# MCU.net
KiCad netlist of a schematic drawn in Altium Designer
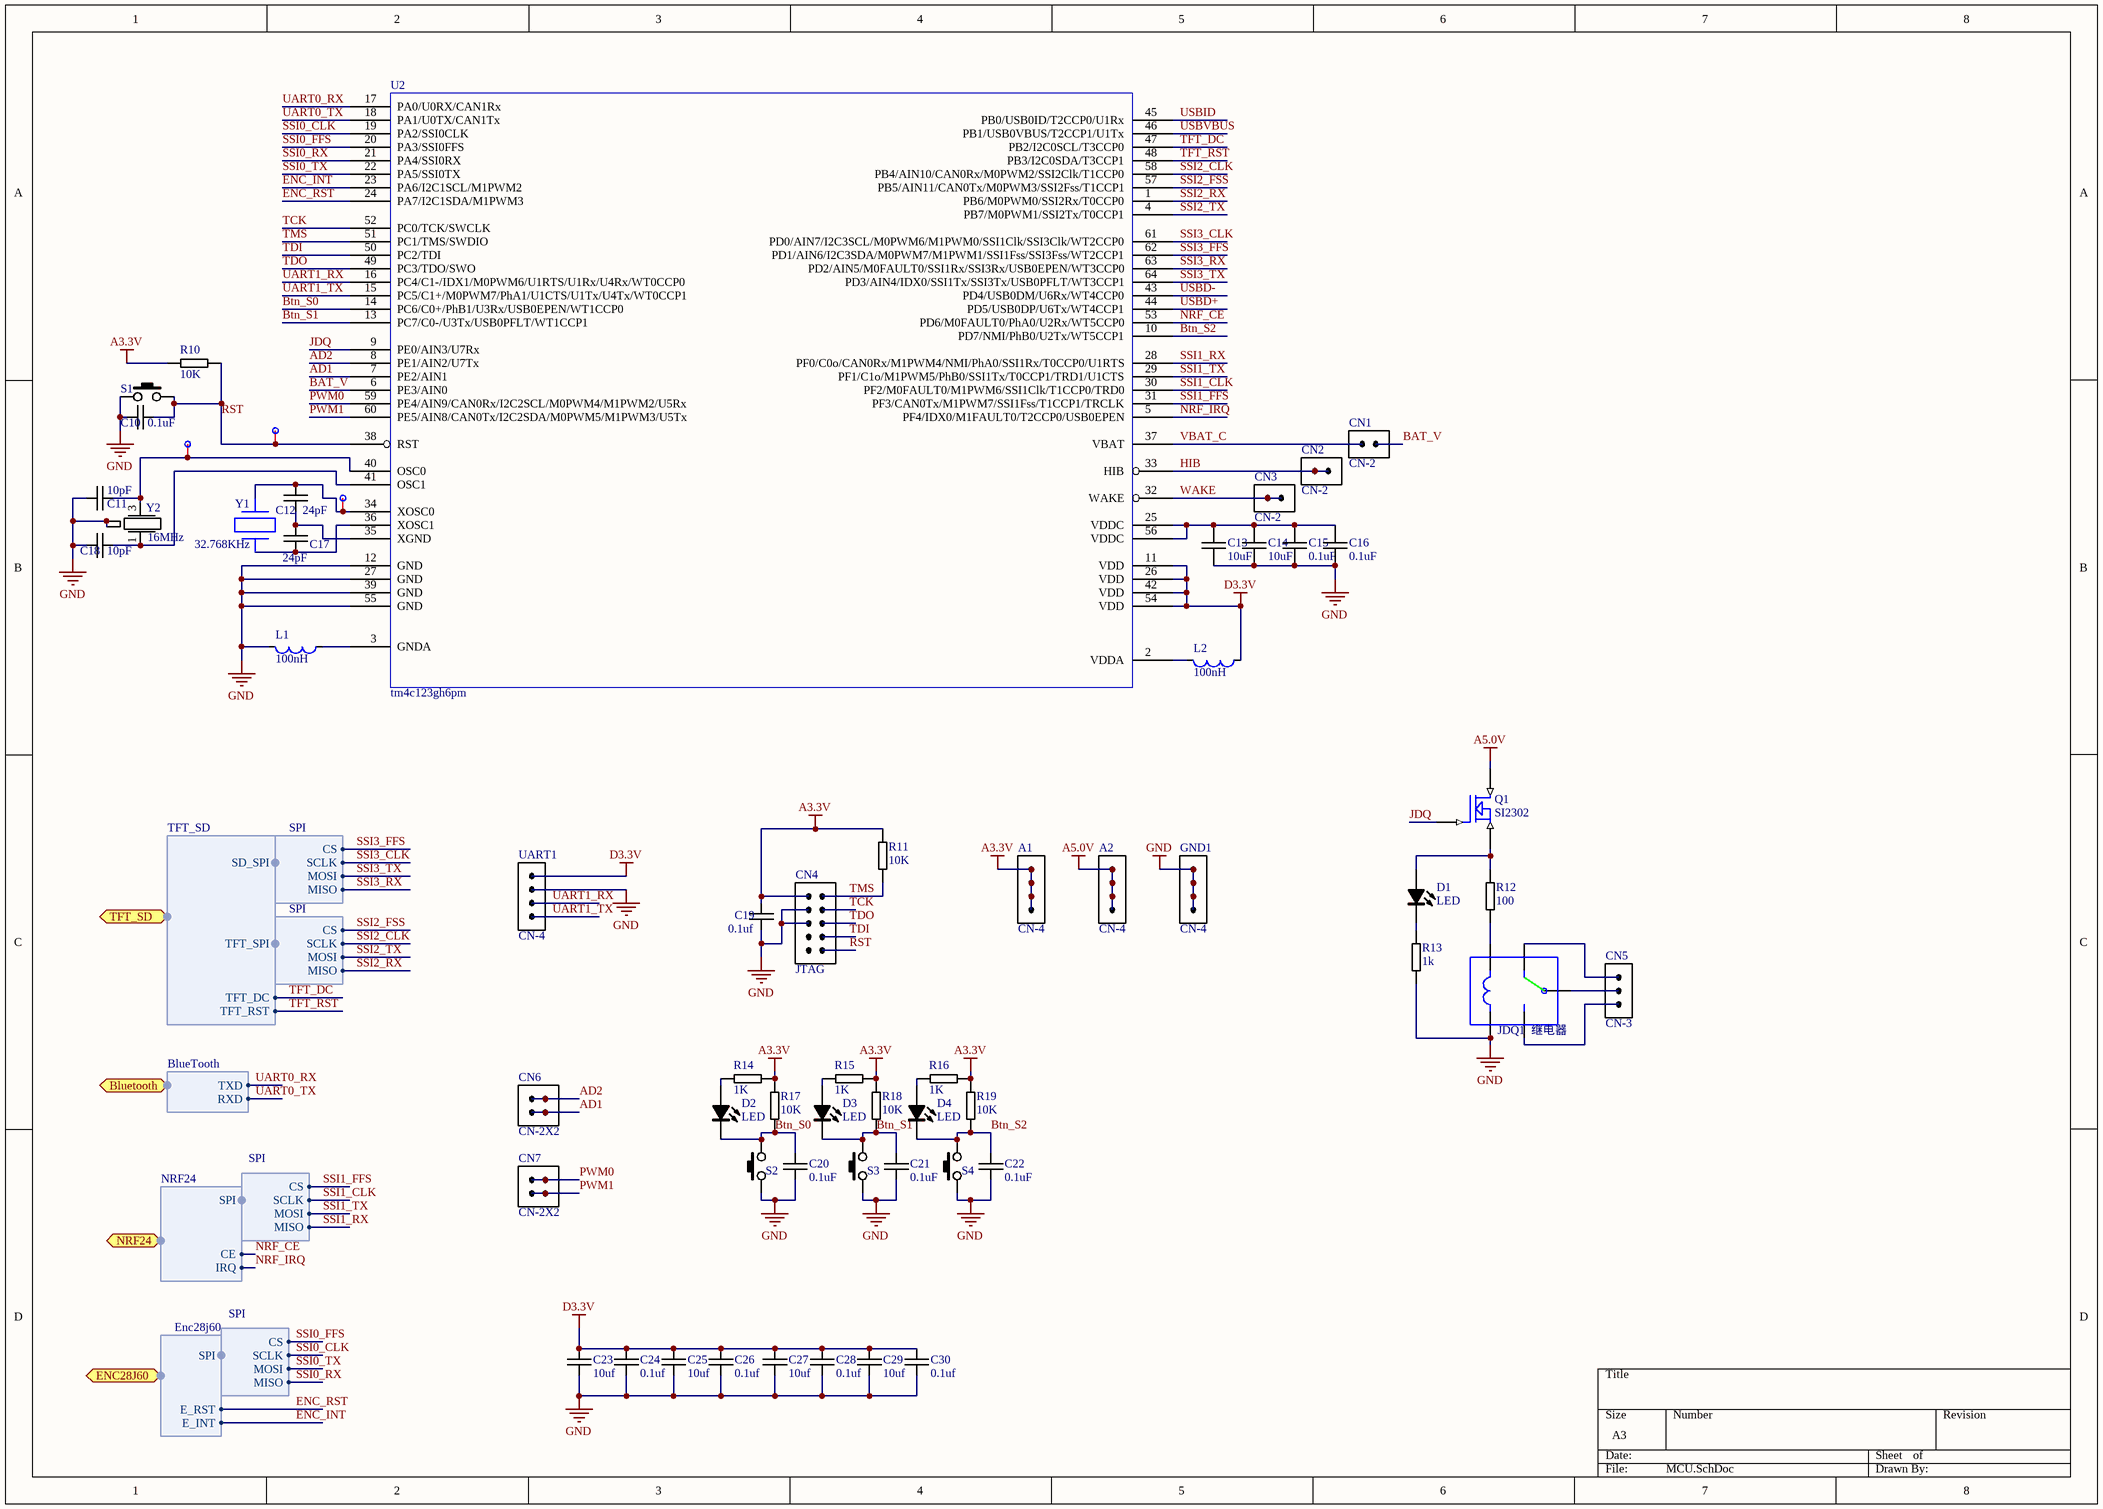
[diagram p0: MCU.SchDoc]

(export (version "E")
  (design (tool "Eeschema 10.0.6"))
  (components
    (comp (ref "*2") (value "Point") (footprint "Point") (libsource (lib "authuir") (part "Point")))
    (comp (ref "*3") (value "Point") (footprint "Point") (libsource (lib "authuir") (part "Point")))
    (comp (ref "*4") (value "Point") (footprint "Point") (libsource (lib "authuir") (part "Point")))
    (comp (ref "A1") (value "CN-4") (footprint "SIP-4") (libsource (lib "开关·连接器") (part "CN-4")))
    (comp (ref "A2") (value "CN-4") (footprint "SIP-4") (libsource (lib "开关·连接器") (part "CN-4")))
    (comp (ref "C10")
      (value "0.1uF")
      (footprint "0805-C")
      (description "贴片")
      (libsource (lib "") (part "CAP_Chip_1"))
    )
    (comp (ref "C11")
      (value "10pF")
      (footprint "0805-C")
      (description "贴片")
      (libsource (lib "") (part "CAP_Chip_1"))
    )
    (comp (ref "C12")
      (value "24pF")
      (footprint "0805-C")
      (description "贴片")
      (libsource (lib "") (part "CAP_Chip_1"))
    )
    (comp (ref "C13")
      (value "10uF")
      (footprint "0805-C")
      (description "贴片")
      (libsource (lib "authuir") (part "CAP_Chip"))
    )
    (comp (ref "C14")
      (value "10uF")
      (footprint "0805-C")
      (description "贴片")
      (libsource (lib "authuir") (part "CAP_Chip"))
    )
    (comp (ref "C15")
      (value "0.1uF")
      (footprint "0805-C")
      (description "贴片")
      (libsource (lib "authuir") (part "CAP_Chip"))
    )
    (comp (ref "C16")
      (value "0.1uF")
      (footprint "0805-C")
      (description "贴片")
      (libsource (lib "authuir") (part "CAP_Chip"))
    )
    (comp (ref "C17")
      (value "24pF")
      (footprint "0805-C")
      (description "贴片")
      (libsource (lib "") (part "CAP_Chip_1"))
    )
    (comp (ref "C18")
      (value "10pF")
      (footprint "0805-C")
      (description "贴片")
      (libsource (lib "") (part "CAP_Chip_1"))
    )
    (comp (ref "C19")
      (value "0.1uf")
      (footprint "0805-C")
      (description "贴片")
      (libsource (lib "") (part "CAP_Chip_1"))
    )
    (comp (ref "C20")
      (value "0.1uF")
      (footprint "0805-C")
      (description "贴片")
      (libsource (lib "") (part "CAP_Chip_1"))
    )
    (comp (ref "C21")
      (value "0.1uF")
      (footprint "0805-C")
      (description "贴片")
      (libsource (lib "") (part "CAP_Chip_1"))
    )
    (comp (ref "C22")
      (value "0.1uF")
      (footprint "0805-C")
      (description "贴片")
      (libsource (lib "") (part "CAP_Chip_1"))
    )
    (comp (ref "C23")
      (value "10uf")
      (footprint "0603")
      (description "贴片")
      (libsource (lib "") (part "CAP_Chip_1"))
    )
    (comp (ref "C24")
      (value "0.1uf")
      (footprint "0603")
      (description "贴片")
      (libsource (lib "") (part "CAP_Chip_1"))
    )
    (comp (ref "C25")
      (value "10uf")
      (footprint "0603")
      (description "贴片")
      (libsource (lib "") (part "CAP_Chip_1"))
    )
    (comp (ref "C26")
      (value "0.1uf")
      (footprint "0603")
      (description "贴片")
      (libsource (lib "") (part "CAP_Chip_1"))
    )
    (comp (ref "C27")
      (value "10uf")
      (footprint "0603")
      (description "贴片")
      (libsource (lib "") (part "CAP_Chip_1"))
    )
    (comp (ref "C28")
      (value "0.1uf")
      (footprint "0603")
      (description "贴片")
      (libsource (lib "") (part "CAP_Chip_1"))
    )
    (comp (ref "C29")
      (value "10uf")
      (footprint "0603")
      (description "贴片")
      (libsource (lib "") (part "CAP_Chip_1"))
    )
    (comp (ref "C30")
      (value "0.1uf")
      (footprint "0603")
      (description "贴片")
      (libsource (lib "") (part "CAP_Chip_1"))
    )
    (comp (ref "CN1") (value "CN-2") (footprint "SIP-2") (libsource (lib "开关·连接器") (part "CN-2")))
    (comp (ref "CN2") (value "CN-2") (footprint "SIP-2") (libsource (lib "开关·连接器") (part "CN-2")))
    (comp (ref "CN3") (value "CN-2") (footprint "SIP-2") (libsource (lib "开关·连接器") (part "CN-2")))
    (comp (ref "CN4") (value "JTAG") (footprint "IDC-10") (libsource (lib "开关·连接器") (part "CN-5X2")))
    (comp (ref "CN5") (value "CN-3") (footprint "SIP-3") (libsource (lib "开关·连接器") (part "CN-3")))
    (comp (ref "CN6") (value "CN-2X2") (footprint "IDC-4") (libsource (lib "开关·连接器") (part "CN-2X2")))
    (comp (ref "CN7") (value "CN-2X2") (footprint "IDC-4") (libsource (lib "开关·连接器") (part "CN-2X2")))
    (comp (ref "D1")
      (value "LED")
      (footprint "0805-LED")
      (description "贴片")
      (libsource (lib "authuir") (part "LED"))
    )
    (comp (ref "D2")
      (value "LED")
      (footprint "0805-LED")
      (description "贴片")
      (libsource (lib "authuir") (part "LED"))
    )
    (comp (ref "D3")
      (value "LED")
      (footprint "0805-LED")
      (description "贴片")
      (libsource (lib "authuir") (part "LED"))
    )
    (comp (ref "D4")
      (value "LED")
      (footprint "0805-LED")
      (description "贴片")
      (libsource (lib "authuir") (part "LED"))
    )
    (comp (ref "GND1") (value "CN-4") (footprint "SIP-4") (libsource (lib "开关·连接器") (part "CN-4")))
    (comp (ref "JDQ1") (value "继电器") (footprint "继电器") (libsource (lib "authuir") (part "继电器")))
    (comp (ref "L1") (value "100nH") (footprint "0805") (libsource (lib "authuir") (part "L")))
    (comp (ref "L2") (value "100nH") (footprint "0805") (libsource (lib "authuir") (part "L")))
    (comp (ref "Q1") (value "SI2302") (footprint "sot-23") (libsource (lib "authuir") (part "SI2302")))
    (comp (ref "R10")
      (value "10K")
      (footprint "0805-R")
      (description "贴片")
      (libsource (lib "authuir") (part "RES_Chip"))
    )
    (comp (ref "R11")
      (value "10K")
      (footprint "0805-R")
      (description "贴片")
      (libsource (lib "authuir") (part "RES_Chip"))
    )
    (comp (ref "R12")
      (value "100")
      (footprint "0603")
      (description "贴片")
      (libsource (lib "authuir") (part "RES_Chip"))
    )
    (comp (ref "R13")
      (value "1k")
      (footprint "0805-R")
      (description "贴片")
      (libsource (lib "authuir") (part "RES_Chip"))
    )
    (comp (ref "R14")
      (value "1K")
      (footprint "0805-R")
      (description "贴片")
      (libsource (lib "authuir") (part "RES_Chip"))
    )
    (comp (ref "R15")
      (value "1K")
      (footprint "0805-R")
      (description "贴片")
      (libsource (lib "authuir") (part "RES_Chip"))
    )
    (comp (ref "R16")
      (value "1K")
      (footprint "0805-R")
      (description "贴片")
      (libsource (lib "authuir") (part "RES_Chip"))
    )
    (comp (ref "R17")
      (value "10K")
      (footprint "0805-R")
      (description "贴片")
      (libsource (lib "authuir") (part "RES_Chip"))
    )
    (comp (ref "R18")
      (value "10K")
      (footprint "0805-R")
      (description "贴片")
      (libsource (lib "authuir") (part "RES_Chip"))
    )
    (comp (ref "R19")
      (value "10K")
      (footprint "0805-R")
      (description "贴片")
      (libsource (lib "authuir") (part "RES_Chip"))
    )
    (comp (ref "S1")
      (value "KEY(轻触,6×6×4.3)")
      (footprint "轻触开关(3*6*2.5)")
      (description "1.09.02.0001")
      (libsource (lib "authuir") (part "KEY(轻触,6×6×4.3)"))
    )
    (comp (ref "S2")
      (value "KEY(轻触,6×6×4.3)")
      (footprint "轻触开关(3*6*2.5)")
      (description "1.09.02.0001")
      (libsource (lib "authuir") (part "KEY(轻触,6×6×4.3)"))
    )
    (comp (ref "S3")
      (value "KEY(轻触,6×6×4.3)")
      (footprint "轻触开关(3*6*2.5)")
      (description "1.09.02.0001")
      (libsource (lib "authuir") (part "KEY(轻触,6×6×4.3)"))
    )
    (comp (ref "S4")
      (value "KEY(轻触,6×6×4.3)")
      (footprint "轻触开关(3*6*2.5)")
      (description "1.09.02.0001")
      (libsource (lib "authuir") (part "KEY(轻触,6×6×4.3)"))
    )
    (comp (ref "U2")
      (value "tm4c123gh6pm")
      (footprint "LQFP64")
      (libsource (lib "authuir") (part "tm4c123gh6pm"))
    )
    (comp (ref "UART1") (value "CN-4") (footprint "SIP-4") (libsource (lib "开关·连接器") (part "CN-4")))
    (comp (ref "Y1")
      (value "32.768KHz")
      (footprint "XTAL(Φ2×6)")
      (libsource (lib "authuir") (part "XTAL_32_768"))
    )
    (comp (ref "Y2") (value "16MHz") (footprint "4脚晶振") (libsource (lib "authuir") (part "XTAL_16M")))
  )
  (nets
    (net (code "5") (name "/AD1") (class "Default")
      (node (ref "CN6") (pin "3") (pinfunction "3_3") (pintype "passive"))
      (node (ref "CN6") (pin "4") (pinfunction "4_4") (pintype "passive"))
      (node (ref "U2") (pin "7") (pinfunction "PE2/AIN1_7") (pintype "passive"))
    )
    (net (code "6") (name "/AD2") (class "Default")
      (node (ref "CN6") (pin "1") (pinfunction "1_1") (pintype "passive"))
      (node (ref "CN6") (pin "2") (pinfunction "2_2") (pintype "passive"))
      (node (ref "U2") (pin "8") (pinfunction "PE1/AIN2/U7Tx_8") (pintype "passive"))
    )
    (net (code "7") (name "/BAT_V") (class "Default")
      (node (ref "CN1") (pin "2") (pinfunction "2_2") (pintype "passive"))
      (node (ref "U2") (pin "6") (pinfunction "PE3/AIN0_6") (pintype "passive"))
    )
    (net (code "8") (name "/Btn_S0") (class "Default")
      (node (ref "C20") (pin "2") (pinfunction "2_2") (pintype "passive"))
      (node (ref "D2") (pin "2") (pinfunction "K_2") (pintype "passive"))
      (node (ref "R17") (pin "2") (pinfunction "2_2") (pintype "passive"))
      (node (ref "S2") (pin "2") (pinfunction "2_2") (pintype "passive"))
      (node (ref "U2") (pin "14") (pinfunction "PC6/C0+/PhB1/U3Rx/USB0EPEN/WT1CCP0_14") (pintype "passive"))
    )
    (net (code "9") (name "/Btn_S1") (class "Default")
      (node (ref "C21") (pin "2") (pinfunction "2_2") (pintype "passive"))
      (node (ref "D3") (pin "2") (pinfunction "K_2") (pintype "passive"))
      (node (ref "R18") (pin "2") (pinfunction "2_2") (pintype "passive"))
      (node (ref "S3") (pin "2") (pinfunction "2_2") (pintype "passive"))
      (node (ref "U2") (pin "13") (pinfunction "PC7/C0-/U3Tx/USB0PFLT/WT1CCP1_13") (pintype "passive"))
    )
    (net (code "10") (name "/Btn_S2") (class "Default")
      (node (ref "C22") (pin "2") (pinfunction "2_2") (pintype "passive"))
      (node (ref "D4") (pin "2") (pinfunction "K_2") (pintype "passive"))
      (node (ref "R19") (pin "2") (pinfunction "2_2") (pintype "passive"))
      (node (ref "S4") (pin "2") (pinfunction "2_2") (pintype "passive"))
      (node (ref "U2") (pin "10") (pinfunction "PD7/NMI/PhB0/U2Tx/WT5CCP1_10") (pintype "passive"))
    )
    (net (code "11") (name "/ENC_INT") (class "Default")
      (node (ref "U2") (pin "23") (pinfunction "PA6/I2C1SCL/M1PWM2_23") (pintype "passive"))
    )
    (net (code "12") (name "/ENC_RST") (class "Default")
      (node (ref "U2") (pin "24") (pinfunction "PA7/I2C1SDA/M1PWM3_24") (pintype "passive"))
    )
    (net (code "13") (name "/HIB") (class "Default")
      (node (ref "CN2") (pin "1") (pinfunction "1_1") (pintype "passive"))
      (node (ref "CN2") (pin "2") (pinfunction "2_2") (pintype "passive"))
      (node (ref "U2") (pin "33") (pinfunction "HIB_33") (pintype "passive"))
    )
    (net (code "14") (name "/JDQ") (class "Default")
      (node (ref "Q1") (pin "1") (pinfunction "G_1") (pintype "input"))
      (node (ref "U2") (pin "9") (pinfunction "PE0/AIN3/U7Rx_9") (pintype "passive"))
    )
    (net (code "15") (name "/NRF_CE") (class "Default")
      (node (ref "U2") (pin "53") (pinfunction "PD6/M0FAULT0/PhA0/U2Rx/WT5CCP0_53") (pintype "passive"))
    )
    (net (code "16") (name "/NRF_IRQ") (class "Default")
      (node (ref "U2") (pin "5") (pinfunction "PF4/IDX0/M1FAULT0/T2CCP0/USB0EPEN_5") (pintype "passive"))
    )
    (net (code "17") (name "/PWM0") (class "Default")
      (node (ref "CN7") (pin "1") (pinfunction "1_1") (pintype "passive"))
      (node (ref "CN7") (pin "2") (pinfunction "2_2") (pintype "passive"))
      (node (ref "U2") (pin "59") (pinfunction "PE4/AIN9/CAN0Rx/I2C2SCL/M0PWM4/M1PWM2/U5Rx_59") (pintype "passive"))
    )
    (net (code "18") (name "/PWM1") (class "Default")
      (node (ref "CN7") (pin "3") (pinfunction "3_3") (pintype "passive"))
      (node (ref "CN7") (pin "4") (pinfunction "4_4") (pintype "passive"))
      (node (ref "U2") (pin "60") (pinfunction "PE5/AIN8/CAN0Tx/I2C2SDA/M0PWM5/M1PWM3/U5Tx_60") (pintype "passive"))
    )
    (net (code "19") (name "/RST") (class "Default")
      (node (ref "*2") (pin "1") (pinfunction "Point_1") (pintype "passive"))
      (node (ref "C10") (pin "2") (pinfunction "2_2") (pintype "passive"))
      (node (ref "CN4") (pin "10") (pinfunction "10_10") (pintype "passive"))
      (node (ref "R10") (pin "1") (pinfunction "1_1") (pintype "passive"))
      (node (ref "S1") (pin "2") (pinfunction "2_2") (pintype "passive"))
      (node (ref "U2") (pin "38") (pinfunction "RST_38") (pintype "passive"))
    )
    (net (code "20") (name "/SSI0_CLK") (class "Default")
      (node (ref "U2") (pin "19") (pinfunction "PA2/SSI0CLK_19") (pintype "passive"))
    )
    (net (code "21") (name "/SSI0_FFS") (class "Default")
      (node (ref "U2") (pin "20") (pinfunction "PA3/SSI0FFS_20") (pintype "passive"))
    )
    (net (code "22") (name "/SSI0_RX") (class "Default")
      (node (ref "U2") (pin "21") (pinfunction "PA4/SSI0RX_21") (pintype "passive"))
    )
    (net (code "23") (name "/SSI0_TX") (class "Default")
      (node (ref "U2") (pin "22") (pinfunction "PA5/SSI0TX_22") (pintype "passive"))
    )
    (net (code "24") (name "/SSI1_CLK") (class "Default")
      (node (ref "U2") (pin "30") (pinfunction "PF2/M0FAULT0/M1PWM6/SSI1Clk/T1CCP0/TRD0_30") (pintype "passive"))
    )
    (net (code "25") (name "/SSI1_FFS") (class "Default")
      (node (ref "U2") (pin "31") (pinfunction "PF3/CAN0Tx/M1PWM7/SSI1Fss/T1CCP1/TRCLK_31") (pintype "passive"))
    )
    (net (code "26") (name "/SSI1_RX") (class "Default")
      (node (ref "U2") (pin "28") (pinfunction "PF0/C0o/CAN0Rx/M1PWM4/NMI/PhA0/SSI1Rx/T0CCP0/U1RTS_28") (pintype "passive"))
    )
    (net (code "27") (name "/SSI1_TX") (class "Default")
      (node (ref "U2") (pin "29") (pinfunction "PF1/C1o/M1PWM5/PhB0/SSI1Tx/T0CCP1/TRD1/U1CTS_29") (pintype "passive"))
    )
    (net (code "28") (name "/SSI2_CLK") (class "Default")
      (node (ref "U2") (pin "58") (pinfunction "PB4/AIN10/CAN0Rx/M0PWM2/SSI2Clk/T1CCP0_58") (pintype "passive"))
    )
    (net (code "29") (name "/SSI2_FSS") (class "Default")
      (node (ref "U2") (pin "57") (pinfunction "PB5/AIN11/CAN0Tx/M0PWM3/SSI2Fss/T1CCP1_57") (pintype "passive"))
    )
    (net (code "30") (name "/SSI2_RX") (class "Default")
      (node (ref "U2") (pin "1") (pinfunction "PB6/M0PWM0/SSI2Rx/T0CCP0_1") (pintype "passive"))
    )
    (net (code "31") (name "/SSI2_TX") (class "Default")
      (node (ref "U2") (pin "4") (pinfunction "PB7/M0PWM1/SSI2Tx/T0CCP1_4") (pintype "passive"))
    )
    (net (code "32") (name "/SSI3_CLK") (class "Default")
      (node (ref "U2") (pin "61") (pinfunction "PD0/AIN7/I2C3SCL/M0PWM6/M1PWM0/SSI1Clk/SSI3Clk/WT2CCP0_61") (pintype "passive"))
    )
    (net (code "33") (name "/SSI3_FFS") (class "Default")
      (node (ref "U2") (pin "62") (pinfunction "PD1/AIN6/I2C3SDA/M0PWM7/M1PWM1/SSI1Fss/SSI3Fss/WT2CCP1_62") (pintype "passive"))
    )
    (net (code "34") (name "/SSI3_RX") (class "Default")
      (node (ref "U2") (pin "63") (pinfunction "PD2/AIN5/M0FAULT0/SSI1Rx/SSI3Rx/USB0EPEN/WT3CCP0_63") (pintype "passive"))
    )
    (net (code "35") (name "/SSI3_TX") (class "Default")
      (node (ref "U2") (pin "64") (pinfunction "PD3/AIN4/IDX0/SSI1Tx/SSI3Tx/USB0PFLT/WT3CCP1_64") (pintype "passive"))
    )
    (net (code "36") (name "/TCK") (class "Default")
      (node (ref "CN4") (pin "4") (pinfunction "4_4") (pintype "passive"))
      (node (ref "U2") (pin "52") (pinfunction "PC0/TCK/SWCLK_52") (pintype "passive"))
    )
    (net (code "37") (name "/TDI") (class "Default")
      (node (ref "CN4") (pin "8") (pinfunction "8_8") (pintype "passive"))
      (node (ref "U2") (pin "50") (pinfunction "PC2/TDI_50") (pintype "passive"))
    )
    (net (code "38") (name "/TDO") (class "Default")
      (node (ref "CN4") (pin "6") (pinfunction "6_6") (pintype "passive"))
      (node (ref "U2") (pin "49") (pinfunction "PC3/TDO/SWO_49") (pintype "passive"))
    )
    (net (code "39") (name "/TFT_DC") (class "Default")
      (node (ref "U2") (pin "47") (pinfunction "PB2/I2C0SCL/T3CCP0_47") (pintype "passive"))
    )
    (net (code "40") (name "/TFT_RST") (class "Default")
      (node (ref "U2") (pin "48") (pinfunction "PB3/I2C0SDA/T3CCP1_48") (pintype "passive"))
    )
    (net (code "41") (name "/TMS") (class "Default")
      (node (ref "CN4") (pin "2") (pinfunction "2_2") (pintype "passive"))
      (node (ref "R11") (pin "1") (pinfunction "1_1") (pintype "passive"))
      (node (ref "U2") (pin "51") (pinfunction "PC1/TMS/SWDIO_51") (pintype "passive"))
    )
    (net (code "42") (name "/UART0_RX") (class "Default")
      (node (ref "U2") (pin "17") (pinfunction "PA0/U0RX/CAN1Rx_17") (pintype "passive"))
    )
    (net (code "43") (name "/UART0_TX") (class "Default")
      (node (ref "U2") (pin "18") (pinfunction "PA1/U0TX/CAN1Tx_18") (pintype "passive"))
    )
    (net (code "44") (name "/UART1_RX") (class "Default")
      (node (ref "U2") (pin "16") (pinfunction "PC4/C1-/IDX1/M0PWM6/U1RTS/U1Rx/U4Rx/WT0CCP0_16") (pintype "passive"))
      (node (ref "UART1") (pin "3") (pinfunction "3_3") (pintype "passive"))
    )
    (net (code "45") (name "/UART1_TX") (class "Default")
      (node (ref "U2") (pin "15") (pinfunction "PC5/C1+/M0PWM7/PhA1/U1CTS/U1Tx/U4Tx/WT0CCP1_15") (pintype "passive"))
      (node (ref "UART1") (pin "4") (pinfunction "4_4") (pintype "passive"))
    )
    (net (code "46") (name "/USBD+") (class "Default")
      (node (ref "U2") (pin "44") (pinfunction "PD5/USB0DP/U6Tx/WT4CCP1_44") (pintype "passive"))
    )
    (net (code "47") (name "/USBD-") (class "Default")
      (node (ref "U2") (pin "43") (pinfunction "PD4/USB0DM/U6Rx/WT4CCP0_43") (pintype "passive"))
    )
    (net (code "48") (name "/USBID") (class "Default")
      (node (ref "U2") (pin "45") (pinfunction "PB0/USB0ID/T2CCP0/U1Rx_45") (pintype "passive"))
    )
    (net (code "49") (name "/USBVBUS") (class "Default")
      (node (ref "U2") (pin "46") (pinfunction "PB1/USB0VBUS/T2CCP1/U1Tx_46") (pintype "passive"))
    )
    (net (code "50") (name "/VBAT_C") (class "Default")
      (node (ref "CN1") (pin "1") (pinfunction "1_1") (pintype "passive"))
      (node (ref "U2") (pin "37") (pinfunction "VBAT_37") (pintype "passive"))
    )
    (net (code "51") (name "/WAKE") (class "Default")
      (node (ref "CN3") (pin "1") (pinfunction "1_1") (pintype "passive"))
      (node (ref "CN3") (pin "2") (pinfunction "2_2") (pintype "passive"))
      (node (ref "U2") (pin "32") (pinfunction "WAKE_32") (pintype "passive"))
    )
    (net (code "56") (name "A3.3V") (class "Default")
      (node (ref "A1") (pin "1") (pinfunction "1_1") (pintype "passive"))
      (node (ref "A1") (pin "2") (pinfunction "2_2") (pintype "passive"))
      (node (ref "A1") (pin "3") (pinfunction "3_3") (pintype "passive"))
      (node (ref "A1") (pin "4") (pinfunction "4_4") (pintype "passive"))
      (node (ref "C19") (pin "1") (pinfunction "1_1") (pintype "passive"))
      (node (ref "CN4") (pin "1") (pinfunction "1_1") (pintype "passive"))
      (node (ref "R10") (pin "2") (pinfunction "2_2") (pintype "passive"))
      (node (ref "R11") (pin "2") (pinfunction "2_2") (pintype "passive"))
      (node (ref "R14") (pin "2") (pinfunction "2_2") (pintype "passive"))
      (node (ref "R15") (pin "2") (pinfunction "2_2") (pintype "passive"))
      (node (ref "R16") (pin "2") (pinfunction "2_2") (pintype "passive"))
      (node (ref "R17") (pin "1") (pinfunction "1_1") (pintype "passive"))
      (node (ref "R18") (pin "1") (pinfunction "1_1") (pintype "passive"))
      (node (ref "R19") (pin "1") (pinfunction "1_1") (pintype "passive"))
    )
    (net (code "57") (name "A5.0V") (class "Default")
      (node (ref "A2") (pin "1") (pinfunction "1_1") (pintype "passive"))
      (node (ref "A2") (pin "2") (pinfunction "2_2") (pintype "passive"))
      (node (ref "A2") (pin "3") (pinfunction "3_3") (pintype "passive"))
      (node (ref "A2") (pin "4") (pinfunction "4_4") (pintype "passive"))
      (node (ref "Q1") (pin "3") (pinfunction "D_3") (pintype "input"))
    )
    (net (code "58") (name "D3.3V") (class "Default")
      (node (ref "C23") (pin "1") (pinfunction "1_1") (pintype "passive"))
      (node (ref "C24") (pin "1") (pinfunction "1_1") (pintype "passive"))
      (node (ref "C25") (pin "1") (pinfunction "1_1") (pintype "passive"))
      (node (ref "C26") (pin "1") (pinfunction "1_1") (pintype "passive"))
      (node (ref "C27") (pin "1") (pinfunction "1_1") (pintype "passive"))
      (node (ref "C28") (pin "1") (pinfunction "1_1") (pintype "passive"))
      (node (ref "C29") (pin "1") (pinfunction "1_1") (pintype "passive"))
      (node (ref "C30") (pin "1") (pinfunction "1_1") (pintype "passive"))
      (node (ref "L2") (pin "2") (pinfunction "2_2") (pintype "passive"))
      (node (ref "U2") (pin "11") (pinfunction "VDD_11") (pintype "passive"))
      (node (ref "U2") (pin "26") (pinfunction "VDD_26") (pintype "passive"))
      (node (ref "U2") (pin "42") (pinfunction "VDD_42") (pintype "passive"))
      (node (ref "U2") (pin "54") (pinfunction "VDD_54") (pintype "passive"))
      (node (ref "UART1") (pin "1") (pinfunction "1_1") (pintype "passive"))
    )
    (net (code "59") (name "GND") (class "Default")
      (node (ref "C10") (pin "1") (pinfunction "1_1") (pintype "passive"))
      (node (ref "C11") (pin "1") (pinfunction "1_1") (pintype "passive"))
      (node (ref "C13") (pin "2") (pinfunction "2_2") (pintype "passive"))
      (node (ref "C14") (pin "2") (pinfunction "2_2") (pintype "passive"))
      (node (ref "C15") (pin "2") (pinfunction "2_2") (pintype "passive"))
      (node (ref "C16") (pin "2") (pinfunction "2_2") (pintype "passive"))
      (node (ref "C18") (pin "1") (pinfunction "1_1") (pintype "passive"))
      (node (ref "C19") (pin "2") (pinfunction "2_2") (pintype "passive"))
      (node (ref "C20") (pin "1") (pinfunction "1_1") (pintype "passive"))
      (node (ref "C21") (pin "1") (pinfunction "1_1") (pintype "passive"))
      (node (ref "C22") (pin "1") (pinfunction "1_1") (pintype "passive"))
      (node (ref "C23") (pin "2") (pinfunction "2_2") (pintype "passive"))
      (node (ref "C24") (pin "2") (pinfunction "2_2") (pintype "passive"))
      (node (ref "C25") (pin "2") (pinfunction "2_2") (pintype "passive"))
      (node (ref "C26") (pin "2") (pinfunction "2_2") (pintype "passive"))
      (node (ref "C27") (pin "2") (pinfunction "2_2") (pintype "passive"))
      (node (ref "C28") (pin "2") (pinfunction "2_2") (pintype "passive"))
      (node (ref "C29") (pin "2") (pinfunction "2_2") (pintype "passive"))
      (node (ref "C30") (pin "2") (pinfunction "2_2") (pintype "passive"))
      (node (ref "CN4") (pin "3") (pinfunction "3_3") (pintype "passive"))
      (node (ref "CN4") (pin "5") (pinfunction "5_5") (pintype "passive"))
      (node (ref "GND1") (pin "1") (pinfunction "1_1") (pintype "passive"))
      (node (ref "GND1") (pin "2") (pinfunction "2_2") (pintype "passive"))
      (node (ref "GND1") (pin "3") (pinfunction "3_3") (pintype "passive"))
      (node (ref "GND1") (pin "4") (pinfunction "4_4") (pintype "passive"))
      (node (ref "JDQ1") (pin "5") (pinfunction "I2_5") (pintype "passive"))
      (node (ref "L1") (pin "1") (pinfunction "1_1") (pintype "passive"))
      (node (ref "R13") (pin "2") (pinfunction "2_2") (pintype "passive"))
      (node (ref "S1") (pin "1") (pinfunction "1_1") (pintype "passive"))
      (node (ref "S2") (pin "1") (pinfunction "1_1") (pintype "passive"))
      (node (ref "S3") (pin "1") (pinfunction "1_1") (pintype "passive"))
      (node (ref "S4") (pin "1") (pinfunction "1_1") (pintype "passive"))
      (node (ref "U2") (pin "12") (pinfunction "GND_12") (pintype "passive"))
      (node (ref "U2") (pin "27") (pinfunction "GND_27") (pintype "passive"))
      (node (ref "U2") (pin "39") (pinfunction "GND_39") (pintype "passive"))
      (node (ref "U2") (pin "55") (pinfunction "GND_55") (pintype "passive"))
      (node (ref "UART1") (pin "2") (pinfunction "2_2") (pintype "passive"))
      (node (ref "Y2") (pin "2") (pinfunction "G_2") (pintype "passive"))
      (node (ref "Y2") (pin "4") (pinfunction "G_4") (pintype "passive"))
    )
    (net (code "60") (name "Net-(*3-Point)") (class "Default")
      (node (ref "*3") (pin "1") (pinfunction "Point_1") (pintype "passive"))
      (node (ref "C11") (pin "2") (pinfunction "2_2") (pintype "passive"))
      (node (ref "U2") (pin "40") (pinfunction "OSC0_40") (pintype "passive"))
      (node (ref "Y2") (pin "3") (pinfunction "O_3") (pintype "passive"))
    )
    (net (code "61") (name "Net-(*4-Point)") (class "Default")
      (node (ref "*4") (pin "1") (pinfunction "Point_1") (pintype "passive"))
      (node (ref "C12") (pin "1") (pinfunction "1_1") (pintype "passive"))
      (node (ref "U2") (pin "34") (pinfunction "XOSC0_34") (pintype "passive"))
      (node (ref "Y1") (pin "1") (pinfunction "1_1") (pintype "passive"))
    )
    (net (code "62") (name "Net-(C13-Pad1)") (class "Default")
      (node (ref "C13") (pin "1") (pinfunction "1_1") (pintype "passive"))
      (node (ref "C14") (pin "1") (pinfunction "1_1") (pintype "passive"))
      (node (ref "C15") (pin "1") (pinfunction "1_1") (pintype "passive"))
      (node (ref "C16") (pin "1") (pinfunction "1_1") (pintype "passive"))
      (node (ref "U2") (pin "25") (pinfunction "VDDC_25") (pintype "passive"))
      (node (ref "U2") (pin "56") (pinfunction "VDDC_56") (pintype "passive"))
    )
    (net (code "63") (name "Net-(CN5-Pad1)") (class "Default")
      (node (ref "CN5") (pin "1") (pinfunction "1_1") (pintype "passive"))
      (node (ref "JDQ1") (pin "4") (pinfunction "4_4") (pintype "passive"))
    )
    (net (code "64") (name "Net-(CN5-Pad2)") (class "Default")
      (node (ref "CN5") (pin "2") (pinfunction "2_2") (pintype "passive"))
      (node (ref "JDQ1") (pin "1") (pinfunction "1_1") (pintype "passive"))
    )
    (net (code "65") (name "Net-(D1-A)") (class "Default")
      (node (ref "D1") (pin "1") (pinfunction "A_1") (pintype "passive"))
      (node (ref "Q1") (pin "2") (pinfunction "S_2") (pintype "input"))
      (node (ref "R12") (pin "1") (pinfunction "1_1") (pintype "passive"))
    )
    (net (code "66") (name "Net-(D1-K)") (class "Default")
      (node (ref "D1") (pin "2") (pinfunction "K_2") (pintype "passive"))
      (node (ref "R13") (pin "1") (pinfunction "1_1") (pintype "passive"))
    )
    (net (code "67") (name "Net-(D2-A)") (class "Default")
      (node (ref "D2") (pin "1") (pinfunction "A_1") (pintype "passive"))
      (node (ref "R14") (pin "1") (pinfunction "1_1") (pintype "passive"))
    )
    (net (code "68") (name "Net-(D3-A)") (class "Default")
      (node (ref "D3") (pin "1") (pinfunction "A_1") (pintype "passive"))
      (node (ref "R15") (pin "1") (pinfunction "1_1") (pintype "passive"))
    )
    (net (code "69") (name "Net-(D4-A)") (class "Default")
      (node (ref "D4") (pin "1") (pinfunction "A_1") (pintype "passive"))
      (node (ref "R16") (pin "1") (pinfunction "1_1") (pintype "passive"))
    )
    (net (code "70") (name "Net-(JDQ1-5)") (class "Default")
      (node (ref "CN5") (pin "3") (pinfunction "3_3") (pintype "passive"))
      (node (ref "JDQ1") (pin "3") (pinfunction "5_3") (pintype "passive"))
    )
    (net (code "71") (name "Net-(JDQ1-I1)") (class "Default")
      (node (ref "JDQ1") (pin "2") (pinfunction "I1_2") (pintype "passive"))
      (node (ref "R12") (pin "2") (pinfunction "2_2") (pintype "passive"))
    )
    (net (code "72") (name "Net-(U2-GNDA)") (class "Default")
      (node (ref "L1") (pin "2") (pinfunction "2_2") (pintype "passive"))
      (node (ref "U2") (pin "3") (pinfunction "GNDA_3") (pintype "passive"))
    )
    (net (code "73") (name "Net-(U2-OSC1)") (class "Default")
      (node (ref "C18") (pin "2") (pinfunction "2_2") (pintype "passive"))
      (node (ref "U2") (pin "41") (pinfunction "OSC1_41") (pintype "passive"))
      (node (ref "Y2") (pin "1") (pinfunction "O_1") (pintype "passive"))
    )
    (net (code "74") (name "Net-(U2-VDDA)") (class "Default")
      (node (ref "L2") (pin "1") (pinfunction "1_1") (pintype "passive"))
      (node (ref "U2") (pin "2") (pinfunction "VDDA_2") (pintype "passive"))
    )
    (net (code "75") (name "Net-(U2-XGND)") (class "Default")
      (node (ref "C12") (pin "2") (pinfunction "2_2") (pintype "passive"))
      (node (ref "C17") (pin "1") (pinfunction "1_1") (pintype "passive"))
      (node (ref "U2") (pin "35") (pinfunction "XGND_35") (pintype "passive"))
    )
    (net (code "76") (name "Net-(U2-XOSC1)") (class "Default")
      (node (ref "C17") (pin "2") (pinfunction "2_2") (pintype "passive"))
      (node (ref "U2") (pin "36") (pinfunction "XOSC1_36") (pintype "passive"))
      (node (ref "Y1") (pin "2") (pinfunction "2_2") (pintype "passive"))
    )
    (net (code "77") (name "unconnected-(CN4-Pad7)") (class "Default")
      (node (ref "CN4") (pin "7") (pinfunction "7_7") (pintype "passive"))
    )
    (net (code "78") (name "unconnected-(CN4-Pad9)") (class "Default")
      (node (ref "CN4") (pin "9") (pinfunction "9_9") (pintype "passive"))
    )
  )
)
